# Supply.net
KiCad netlist of a schematic drawn in Altium Designer
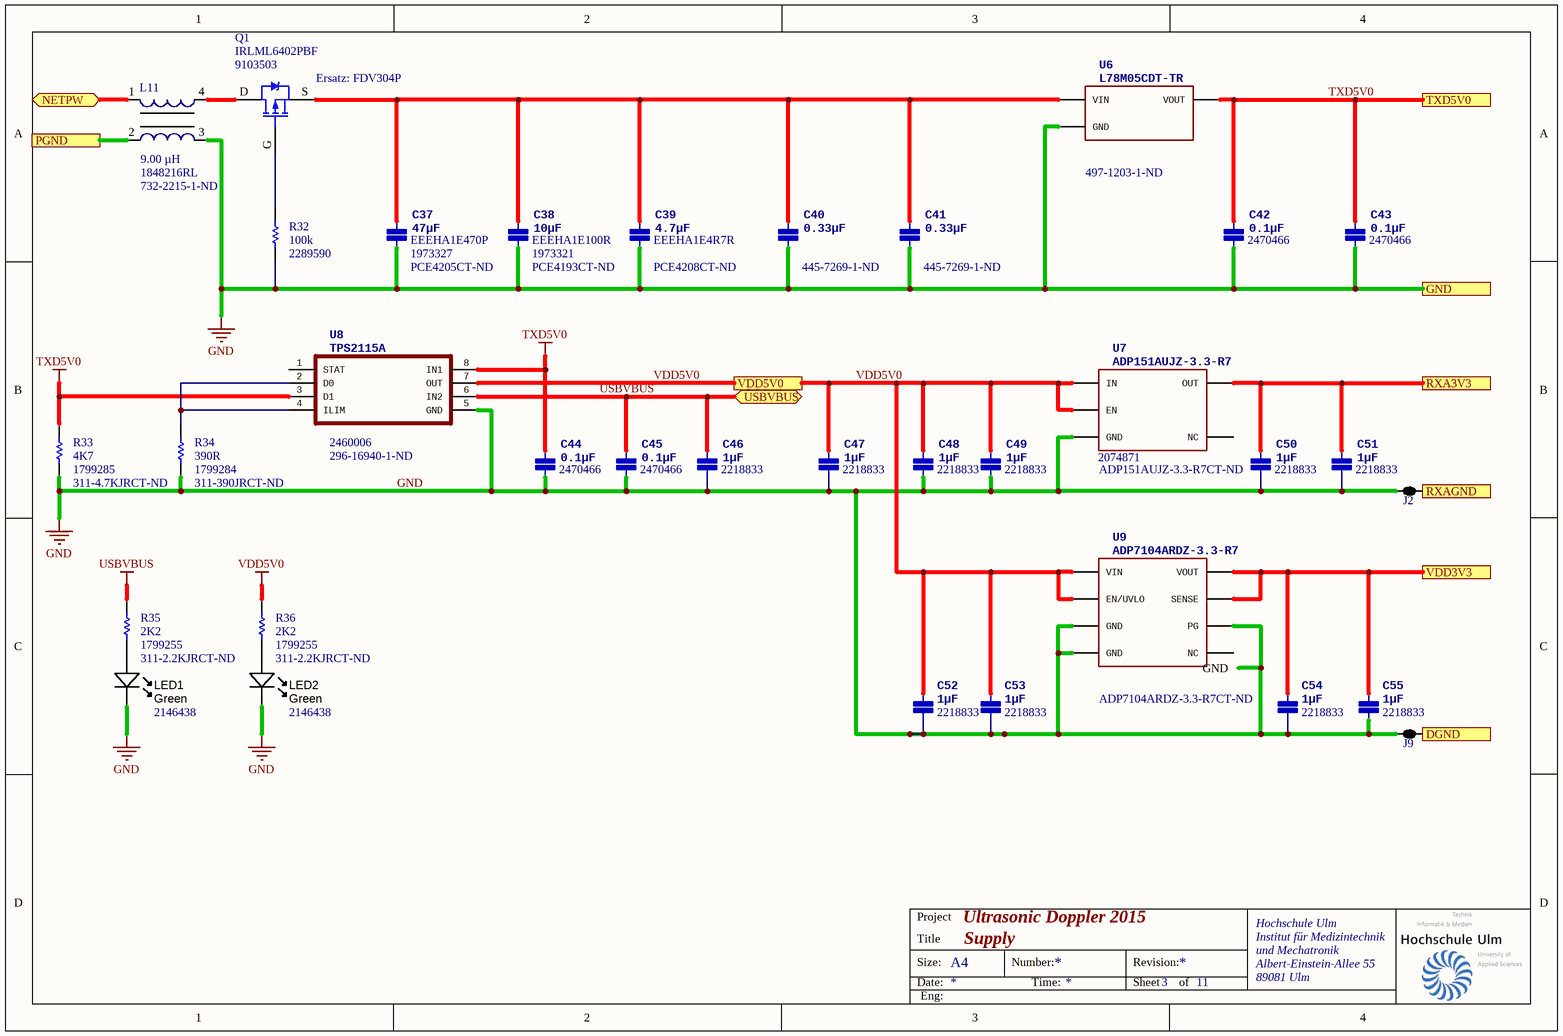
[diagram p0: Supply.SchDoc]

(export (version "E")
  (design (tool "Eeschema 10.0.6"))
  (components
    (comp (ref "C37")
      (value "47µF")
      (footprint "Panasonic Size E")
      (description "Cap Panasonic Size E")
      (fields
        (field (name "PARTNR.") "EEEHA1E470P")
        (field (name "SUPPLIER PART NUMBER 1") "1973327")
        (field (name "SUPPLIER PART NUMBER 2") "PCE4205CT-ND")
      )
      (libsource (lib "Components") (part "Capacitor"))
    )
    (comp (ref "C38")
      (value "10µF")
      (footprint "Panasonic Size C")
      (description "Cap Panasonic Size C")
      (fields
        (field (name "PARTNR.") "EEEHA1E100R")
        (field (name "SUPPLIER PART NUMBER 1") "1973321")
        (field (name "SUPPLIER PART NUMBER 2") "PCE4193CT-ND")
      )
      (libsource (lib "Components") (part "Capacitor"))
    )
    (comp (ref "C39")
      (value "4.7µF")
      (footprint "Panasonic Size B")
      (description "Cap Panasonic Size B")
      (fields (field (name "PARTNR.") "EEEHA1E4R7R") (field (name "SUPPLIER PART NUMBER 1") "PCE4208CT-ND"))
      (libsource (lib "Components") (part "Capacitor"))
    )
    (comp (ref "C40")
      (value "0.33µF")
      (footprint "0603")
      (description "Cap")
      (fields (field (name "SUPPLIER PART NUMBER 1") "445-7269-1-ND"))
      (libsource (lib "Components") (part "Capacitor"))
    )
    (comp (ref "C41")
      (value "0.33µF")
      (footprint "0603")
      (description "Cap")
      (fields (field (name "SUPPLIER PART NUMBER 1") "445-7269-1-ND"))
      (libsource (lib "Components") (part "Capacitor"))
    )
    (comp (ref "C42")
      (value "0.1µF")
      (footprint "0402[1005]")
      (description "Cap")
      (fields (field (name "SUPPLIER PART NUMBER 1") "2470466"))
      (libsource (lib "Components") (part "Capacitor"))
    )
    (comp (ref "C43")
      (value "0.1µF")
      (footprint "0402[1005]")
      (description "Cap")
      (fields (field (name "SUPPLIER PART NUMBER 1") "2470466"))
      (libsource (lib "Components") (part "Capacitor"))
    )
    (comp (ref "C44")
      (value "0.1µF")
      (footprint "0402[1005]")
      (description "Cap")
      (fields (field (name "SUPPLIER PART NUMBER 1") "2470466"))
      (libsource (lib "Components") (part "Capacitor"))
    )
    (comp (ref "C45")
      (value "0.1µF")
      (footprint "0402[1005]")
      (description "Cap")
      (fields (field (name "SUPPLIER PART NUMBER 1") "2470466"))
      (libsource (lib "Components") (part "Capacitor"))
    )
    (comp (ref "C46")
      (value "1µF")
      (footprint "0402[1005]")
      (description "Cap")
      (fields (field (name "SUPPLIER PART NUMBER 1") "2218833"))
      (libsource (lib "Components") (part "Capacitor"))
    )
    (comp (ref "C47")
      (value "1µF")
      (footprint "0402[1005]")
      (description "Cap")
      (fields (field (name "SUPPLIER PART NUMBER 1") "2218833"))
      (libsource (lib "Components") (part "Capacitor"))
    )
    (comp (ref "C48")
      (value "1µF")
      (footprint "0402[1005]")
      (description "Cap")
      (fields (field (name "SUPPLIER PART NUMBER 1") "2218833"))
      (libsource (lib "Components") (part "Capacitor"))
    )
    (comp (ref "C49")
      (value "1µF")
      (footprint "0402[1005]")
      (description "Cap")
      (fields (field (name "SUPPLIER PART NUMBER 1") "2218833"))
      (libsource (lib "Components") (part "Capacitor"))
    )
    (comp (ref "C50")
      (value "1µF")
      (footprint "0402[1005]")
      (description "Cap")
      (fields (field (name "SUPPLIER PART NUMBER 1") "2218833"))
      (libsource (lib "Components") (part "Capacitor"))
    )
    (comp (ref "C51")
      (value "1µF")
      (footprint "0402[1005]")
      (description "Cap")
      (fields (field (name "SUPPLIER PART NUMBER 1") "2218833"))
      (libsource (lib "Components") (part "Capacitor"))
    )
    (comp (ref "C52")
      (value "1µF")
      (footprint "0402[1005]")
      (description "Cap")
      (fields (field (name "SUPPLIER PART NUMBER 1") "2218833"))
      (libsource (lib "Components") (part "Capacitor"))
    )
    (comp (ref "C53")
      (value "1µF")
      (footprint "0402[1005]")
      (description "Cap")
      (fields (field (name "SUPPLIER PART NUMBER 1") "2218833"))
      (libsource (lib "Components") (part "Capacitor"))
    )
    (comp (ref "C54")
      (value "1µF")
      (footprint "0402[1005]")
      (description "Cap")
      (fields (field (name "SUPPLIER PART NUMBER 1") "2218833"))
      (libsource (lib "Components") (part "Capacitor"))
    )
    (comp (ref "C55")
      (value "1µF")
      (footprint "0402[1005]")
      (description "Cap")
      (fields (field (name "SUPPLIER PART NUMBER 1") "2218833"))
      (libsource (lib "Components") (part "Capacitor"))
    )
    (comp (ref "J2")
      (value "2 way net tie junction")
      (footprint "2way_MP")
      (libsource (lib "NetTieLib") (part "2way"))
    )
    (comp (ref "J9")
      (value "2 way net tie junction")
      (footprint "2way_MP")
      (libsource (lib "NetTieLib") (part "2way"))
    )
    (comp (ref "L11")
      (value "9.00 µH")
      (footprint "WE-SL5 HC")
      (description "SMD Common Mode Line Filter WE-SL5 HC, L=9.00 µH")
      (fields
        (field (name "PARTNO") "744273801")
        (field (name "MANUFACTURER") "Würth Elektronik eiSos GmbH")
        (field (name "SUPPLIER PART NUMBER 1") "1848216RL")
        (field (name "SUPPLIER PART NUMBER 2") "732-2215-1-ND")
        (field (name "CREATED BY") "Christin Zierenner")
      )
      (libsource (lib "WE-SL5_HC") (part "WE-SL5 HC, 744273801"))
    )
    (comp (ref "LED1")
      (value "Green")
      (footprint "LED-0603-GREEN")
      (description "LED 0603 SMD Green 525nm 350mcd 20mA")
      (fields (field (name "SUPPLIER PART NUMBER 1") "2146438"))
      (libsource (lib "USD Parts") (part "LED_SMD_Green_0603_525nm_350mcd"))
    )
    (comp (ref "LED2")
      (value "Green")
      (footprint "LED-0603-GREEN")
      (description "LED 0603 SMD Green 525nm 350mcd 20mA")
      (fields (field (name "SUPPLIER PART NUMBER 1") "2146438"))
      (libsource (lib "USD Parts") (part "LED_SMD_Green_0603_525nm_350mcd"))
    )
    (comp (ref "Q1")
      (value "IRLML6402PBF")
      (footprint "SOT23-3")
      (description "P-Channel Power MOSFET")
      (fields (field (name "SUPPLIER PART NUMBER 1") "9103503") (field (name "PUBLISHER") "Altium Limited"))
      (libsource (lib "Components") (part "PMOS-2"))
    )
    (comp (ref "R32")
      (value "100k")
      (footprint "0402[1005]")
      (description "Resistor")
      (fields (field (name "SUPPLIER PART NUMBER 1") "2289590") (field (name "PUBLISHER") "Altium Limited"))
      (libsource (lib "USD Parts") (part "Resistor"))
    )
    (comp (ref "R33")
      (value "4K7")
      (footprint "0402[1005]")
      (description "Resistor")
      (fields
        (field (name "SUPPLIER PART NUMBER 1") "311-4.7KJRCT-ND")
        (field (name "SUPPLIER PART NUMBER 2") "1799285")
        (field (name "PUBLISHER") "Altium Limited")
      )
      (libsource (lib "Components") (part "Resistor"))
    )
    (comp (ref "R34")
      (value "390R")
      (footprint "0402[1005]")
      (description "Resistor")
      (fields
        (field (name "SUPPLIER PART NUMBER 1") "1799284")
        (field (name "SUPPLIER PART NUMBER 2") "311-390JRCT-ND")
        (field (name "PUBLISHER") "Altium Limited")
      )
      (libsource (lib "Components") (part "Resistor"))
    )
    (comp (ref "R35")
      (value "2K2")
      (footprint "0402[1005]")
      (description "Resistor")
      (fields
        (field (name "SUPPLIER PART NUMBER 1") "311-2.2KJRCT-ND")
        (field (name "SUPPLIER PART NUMBER 2") "1799255")
        (field (name "PUBLISHER") "Altium Limited")
      )
      (libsource (lib "Components") (part "Resistor"))
    )
    (comp (ref "R36")
      (value "2K2")
      (footprint "0402[1005]")
      (description "Resistor")
      (fields
        (field (name "SUPPLIER PART NUMBER 1") "311-2.2KJRCT-ND")
        (field (name "SUPPLIER PART NUMBER 2") "1799255")
        (field (name "PUBLISHER") "Altium Limited")
      )
      (libsource (lib "Components") (part "Resistor"))
    )
    (comp (ref "U6")
      (value "L78M05CDT-TR")
      (footprint "DPAK")
      (description "Switch mode power supply")
      (fields (field (name "SUPPLIER PART NUMBER 1") "497-1203-1-ND"))
      (libsource (lib "Components") (part "L78M"))
    )
    (comp (ref "U7")
      (value "ADP151AUJZ-3.3-R7")
      (footprint "SOT23-5-TI")
      (description "LDO")
      (fields
        (field (name "SUPPLIER PART NUMBER 1") "2074871")
        (field (name "SUPPLIER PART NUMBER 2") "ADP151AUJZ-3.3-R7CT-ND")
      )
      (libsource (lib "USD Parts") (part "ADP151"))
    )
    (comp (ref "U8")
      (value "TPS2115A")
      (footprint "TSSOP-8")
      (description "autoswitching power mux")
      (fields
        (field (name "SUPPLIER PART NUMBER 1") "2460006")
        (field (name "SUPPLIER PART NUMBER 2") "296-16940-1-ND")
      )
      (libsource (lib "Components") (part "TPS2115A"))
    )
    (comp (ref "U9")
      (value "ADP7104ARDZ-3.3-R7")
      (footprint "SOIC8_EP")
      (description "LDO")
      (fields (field (name "SUPPLIER PART NUMBER 1") "ADP7104ARDZ-3.3-R7CT-ND"))
      (libsource (lib "USD Parts") (part "ADP7104"))
    )
  )
  (nets
    (net (code "1") (name "/DGND") (class "Default")
      (node (ref "J9") (pin "2") (pinfunction "2_2") (pintype "passive"))
    )
    (net (code "2") (name "/NETPW") (class "Default")
      (node (ref "L11") (pin "1") (pinfunction "1_1") (pintype "passive"))
    )
    (net (code "3") (name "/PGND") (class "Default")
      (node (ref "L11") (pin "2") (pinfunction "2_2") (pintype "passive"))
    )
    (net (code "4") (name "/RXA3V3") (class "Default")
      (node (ref "C50") (pin "1") (pinfunction "P$1_1") (pintype "passive"))
      (node (ref "C51") (pin "1") (pinfunction "P$1_1") (pintype "passive"))
      (node (ref "U7") (pin "5") (pinfunction "OUT_5") (pintype "power_in"))
    )
    (net (code "5") (name "/RXAGND") (class "Default")
      (node (ref "J2") (pin "2") (pinfunction "2_2") (pintype "passive"))
    )
    (net (code "6") (name "/VDD3V3") (class "Default")
      (node (ref "C54") (pin "1") (pinfunction "P$1_1") (pintype "passive"))
      (node (ref "C55") (pin "1") (pinfunction "P$1_1") (pintype "passive"))
      (node (ref "U9") (pin "1") (pinfunction "VOUT_1") (pintype "power_in"))
      (node (ref "U9") (pin "2") (pinfunction "SENSE_2") (pintype "power_in"))
    )
    (net (code "7") (name "GND") (class "Default")
      (node (ref "C37") (pin "2") (pinfunction "P$2_2") (pintype "passive"))
      (node (ref "C38") (pin "2") (pinfunction "P$2_2") (pintype "passive"))
      (node (ref "C39") (pin "2") (pinfunction "P$2_2") (pintype "passive"))
      (node (ref "C40") (pin "2") (pinfunction "P$2_2") (pintype "passive"))
      (node (ref "C41") (pin "2") (pinfunction "P$2_2") (pintype "passive"))
      (node (ref "C42") (pin "2") (pinfunction "P$2_2") (pintype "passive"))
      (node (ref "C43") (pin "2") (pinfunction "P$2_2") (pintype "passive"))
      (node (ref "C44") (pin "2") (pinfunction "P$2_2") (pintype "passive"))
      (node (ref "C45") (pin "2") (pinfunction "P$2_2") (pintype "passive"))
      (node (ref "C46") (pin "2") (pinfunction "P$2_2") (pintype "passive"))
      (node (ref "C47") (pin "2") (pinfunction "P$2_2") (pintype "passive"))
      (node (ref "C48") (pin "2") (pinfunction "P$2_2") (pintype "passive"))
      (node (ref "C49") (pin "2") (pinfunction "P$2_2") (pintype "passive"))
      (node (ref "C50") (pin "2") (pinfunction "P$2_2") (pintype "passive"))
      (node (ref "C51") (pin "2") (pinfunction "P$2_2") (pintype "passive"))
      (node (ref "C52") (pin "2") (pinfunction "P$2_2") (pintype "passive"))
      (node (ref "C53") (pin "2") (pinfunction "P$2_2") (pintype "passive"))
      (node (ref "C54") (pin "2") (pinfunction "P$2_2") (pintype "passive"))
      (node (ref "C55") (pin "2") (pinfunction "P$2_2") (pintype "passive"))
      (node (ref "J2") (pin "1") (pinfunction "1_1") (pintype "passive"))
      (node (ref "J9") (pin "1") (pinfunction "1_1") (pintype "passive"))
      (node (ref "L11") (pin "3") (pinfunction "3_3") (pintype "passive"))
      (node (ref "LED1") (pin "K") (pinfunction "K_K") (pintype "passive"))
      (node (ref "LED2") (pin "K") (pinfunction "K_K") (pintype "passive"))
      (node (ref "R32") (pin "2") (pinfunction "2_2") (pintype "passive"))
      (node (ref "R33") (pin "2") (pinfunction "2_2") (pintype "passive"))
      (node (ref "R34") (pin "2") (pinfunction "2_2") (pintype "passive"))
      (node (ref "U6") (pin "GND") (pinfunction "GND_GND") (pintype "power_in"))
      (node (ref "U7") (pin "2") (pinfunction "GND_2") (pintype "power_in"))
      (node (ref "U8") (pin "5") (pinfunction "GND_5") (pintype "passive"))
      (node (ref "U9") (pin "3") (pinfunction "GND_3") (pintype "power_in"))
      (node (ref "U9") (pin "6") (pinfunction "GND_6") (pintype "power_in"))
      (node (ref "U9") (pin "7") (pinfunction "PG_7") (pintype "power_in"))
      (node (ref "U9") (pin "9") (pinfunction "GND_9") (pintype "power_in"))
    )
    (net (code "8") (name "Net-(C37-P$1)") (class "Default")
      (node (ref "C37") (pin "1") (pinfunction "P$1_1") (pintype "passive"))
      (node (ref "C38") (pin "1") (pinfunction "P$1_1") (pintype "passive"))
      (node (ref "C39") (pin "1") (pinfunction "P$1_1") (pintype "passive"))
      (node (ref "C40") (pin "1") (pinfunction "P$1_1") (pintype "passive"))
      (node (ref "C41") (pin "1") (pinfunction "P$1_1") (pintype "passive"))
      (node (ref "Q1") (pin "S") (pinfunction "S_S") (pintype "passive"))
      (node (ref "U6") (pin "VIN") (pinfunction "VIN_VIN") (pintype "power_in"))
    )
    (net (code "9") (name "Net-(L11-Pad4)") (class "Default")
      (node (ref "L11") (pin "4") (pinfunction "4_4") (pintype "passive"))
      (node (ref "Q1") (pin "D") (pinfunction "D_D") (pintype "passive"))
    )
    (net (code "10") (name "Net-(LED1-PadA)") (class "Default")
      (node (ref "LED1") (pin "A") (pinfunction "A_A") (pintype "passive"))
      (node (ref "R35") (pin "2") (pinfunction "2_2") (pintype "passive"))
    )
    (net (code "11") (name "Net-(LED2-PadA)") (class "Default")
      (node (ref "LED2") (pin "A") (pinfunction "A_A") (pintype "passive"))
      (node (ref "R36") (pin "2") (pinfunction "2_2") (pintype "passive"))
    )
    (net (code "12") (name "Net-(Q1-PadG)") (class "Default")
      (node (ref "Q1") (pin "G") (pinfunction "G_G") (pintype "passive"))
      (node (ref "R32") (pin "1") (pinfunction "1_1") (pintype "passive"))
    )
    (net (code "13") (name "Net-(U8-D0)") (class "Default")
      (node (ref "R34") (pin "1") (pinfunction "1_1") (pintype "passive"))
      (node (ref "U8") (pin "2") (pinfunction "D0_2") (pintype "passive"))
      (node (ref "U8") (pin "4") (pinfunction "ILIM_4") (pintype "passive"))
    )
    (net (code "14") (name "TXD5V0") (class "Default")
      (node (ref "C42") (pin "1") (pinfunction "P$1_1") (pintype "passive"))
      (node (ref "C43") (pin "1") (pinfunction "P$1_1") (pintype "passive"))
      (node (ref "C44") (pin "1") (pinfunction "P$1_1") (pintype "passive"))
      (node (ref "R33") (pin "1") (pinfunction "1_1") (pintype "passive"))
      (node (ref "U6") (pin "VOUT") (pinfunction "VOUT_VOUT") (pintype "power_in"))
      (node (ref "U8") (pin "3") (pinfunction "D1_3") (pintype "passive"))
      (node (ref "U8") (pin "8") (pinfunction "IN1_8") (pintype "passive"))
    )
    (net (code "15") (name "USBVBUS") (class "Default")
      (node (ref "C45") (pin "1") (pinfunction "P$1_1") (pintype "passive"))
      (node (ref "C46") (pin "1") (pinfunction "P$1_1") (pintype "passive"))
      (node (ref "R35") (pin "1") (pinfunction "1_1") (pintype "passive"))
      (node (ref "U8") (pin "6") (pinfunction "IN2_6") (pintype "passive"))
    )
    (net (code "16") (name "VDD5V0") (class "Default")
      (node (ref "C47") (pin "1") (pinfunction "P$1_1") (pintype "passive"))
      (node (ref "C48") (pin "1") (pinfunction "P$1_1") (pintype "passive"))
      (node (ref "C49") (pin "1") (pinfunction "P$1_1") (pintype "passive"))
      (node (ref "C52") (pin "1") (pinfunction "P$1_1") (pintype "passive"))
      (node (ref "C53") (pin "1") (pinfunction "P$1_1") (pintype "passive"))
      (node (ref "R36") (pin "1") (pinfunction "1_1") (pintype "passive"))
      (node (ref "U7") (pin "1") (pinfunction "IN_1") (pintype "power_in"))
      (node (ref "U7") (pin "3") (pinfunction "EN_3") (pintype "power_in"))
      (node (ref "U8") (pin "7") (pinfunction "OUT_7") (pintype "passive"))
      (node (ref "U9") (pin "5") (pinfunction "EN/UVLO_5") (pintype "power_in"))
      (node (ref "U9") (pin "8") (pinfunction "VIN_8") (pintype "power_in"))
    )
    (net (code "17") (name "unconnected-(U7-NC-Pad4)") (class "Default")
      (node (ref "U7") (pin "4") (pinfunction "NC_4") (pintype "power_in"))
    )
    (net (code "18") (name "unconnected-(U8-STAT-Pad1)") (class "Default")
      (node (ref "U8") (pin "1") (pinfunction "STAT_1") (pintype "passive"))
    )
    (net (code "19") (name "unconnected-(U9-NC-Pad4)") (class "Default")
      (node (ref "U9") (pin "4") (pinfunction "NC_4") (pintype "power_in"))
    )
  )
)
